# spectrometer-teensy-mk-1_0_0.net
KiCad netlist of a schematic drawn in EAGLE
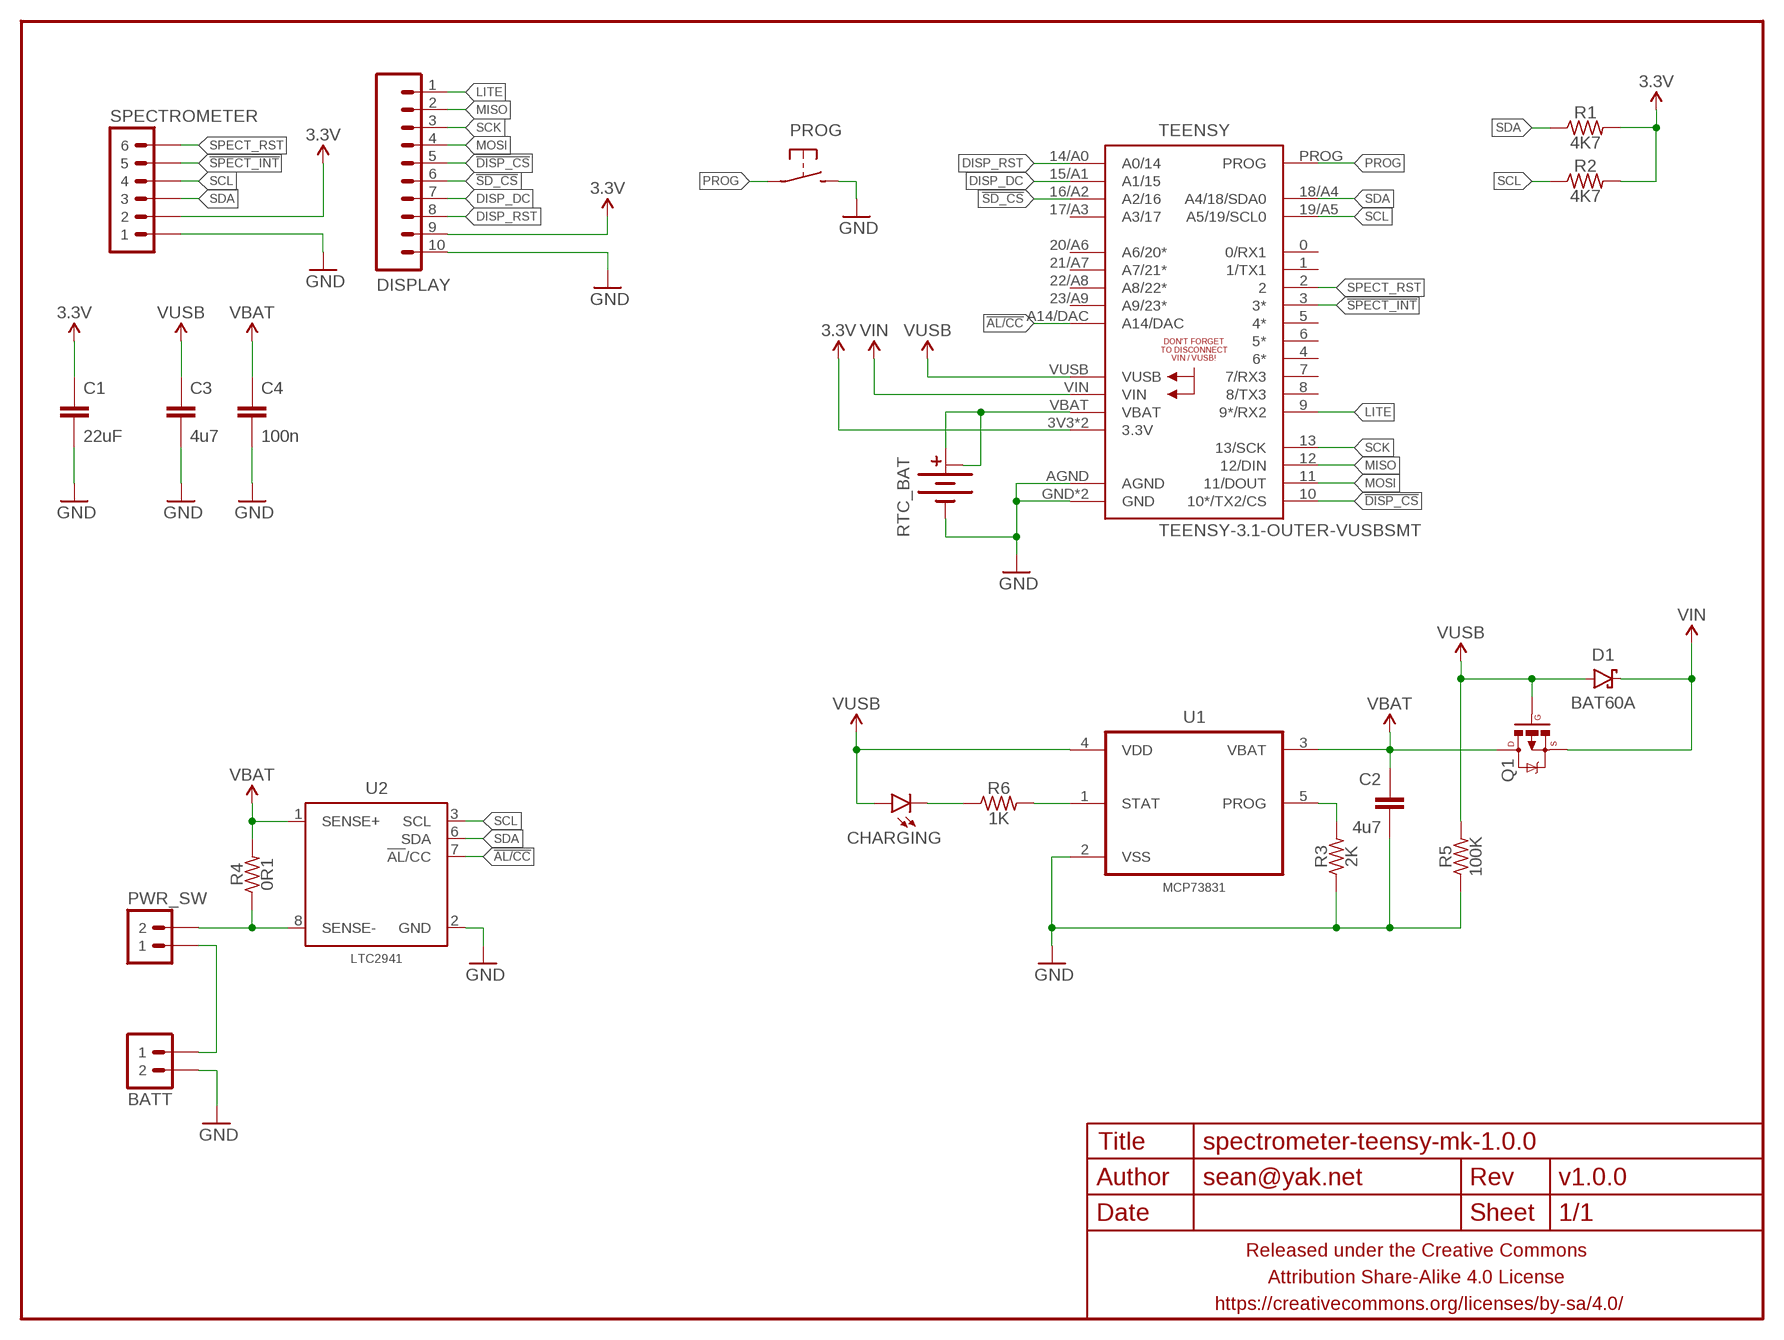
[diagram p0: schematic, sheet 1]

(export (version "E")
  (design (tool "Eeschema 10.0.6"))
  (components
    (comp (ref "BATT")
      (value "M02JST-2MM-SMT")
      (footprint "eagle-import:JST-2-SMD")
      (libsource (lib "eagle-import") (part "M02JST-2MM-SMT"))
    )
    (comp (ref "C1")
      (value "22uF")
      (footprint "eagle-import:C0805-TIGHTER")
      (libsource (lib "eagle-import") (part "CAPACITOR-CERAMICC0805-TIGHTER"))
    )
    (comp (ref "C2")
      (value "4u7")
      (footprint "eagle-import:C0603-TIGHTER")
      (libsource (lib "eagle-import") (part "CAPACITOR-CERAMICC0603-TIGHTER"))
    )
    (comp (ref "C3")
      (value "4u7")
      (footprint "eagle-import:C0603-TIGHTER")
      (libsource (lib "eagle-import") (part "CAPACITOR-CERAMICC0603-TIGHTER"))
    )
    (comp (ref "C4")
      (value "100n")
      (footprint "eagle-import:C0603-TIGHTER")
      (libsource (lib "eagle-import") (part "CAPACITOR-CERAMICC0603-TIGHTER"))
    )
    (comp (ref "CHARGING")
      (value "LED0603-TIGHT")
      (footprint "eagle-import:LED-0603-TIGHT")
      (libsource (lib "eagle-import") (part "LED0603-TIGHT"))
    )
    (comp (ref "D1")
      (value "BAT60A")
      (footprint "eagle-import:SOD123-SCHOTTKY")
      (libsource (lib "eagle-import") (part "DIODE-SCHOTTKYSOD123"))
    )
    (comp (ref "DISPLAY")
      (value "M10SMD_RA_2MM")
      (footprint "eagle-import:1X10_SMD_RA_MALE")
      (libsource (lib "eagle-import") (part "M10SMD_RA_2MM"))
    )
    (comp (ref "FRAME1")
      (value "FRAME-LETTERNO_PACKAGE")
      (footprint "eagle-import:DUMMY")
      (fields (field (name "DESIGNER") "sean@yak.net") (field (name "VERSION") "v1.0.0"))
      (libsource (lib "eagle-import") (part "FRAME-LETTERNO_PACKAGE"))
    )
    (comp (ref "PROG")
      (value "SPST-NO-TACTCK-PTS840-GK")
      (footprint "eagle-import:TACTILE-SMD-CK-PTS840-GK")
      (libsource (lib "eagle-import") (part "SPST-NO-TACTCK-PTS840-GK"))
    )
    (comp (ref "PWR_SW")
      (value "M02JST-2MM-SMT")
      (footprint "eagle-import:JST-2-SMD")
      (libsource (lib "eagle-import") (part "M02JST-2MM-SMT"))
    )
    (comp (ref "Q1")
      (value "MOSFET-PCHANNELSOT-23")
      (footprint "eagle-import:SOT23")
      (libsource (lib "eagle-import") (part "MOSFET-PCHANNELSOT-23"))
    )
    (comp (ref "R1")
      (value "4K7")
      (footprint "eagle-import:R0603-TIGHTER")
      (libsource (lib "eagle-import") (part "RESISTORR0603-TIGHTER"))
    )
    (comp (ref "R2")
      (value "4K7")
      (footprint "eagle-import:R0603-TIGHTER")
      (libsource (lib "eagle-import") (part "RESISTORR0603-TIGHTER"))
    )
    (comp (ref "R3")
      (value "2K")
      (footprint "eagle-import:R0603-TIGHTER")
      (libsource (lib "eagle-import") (part "RESISTORR0603-TIGHTER"))
    )
    (comp (ref "R4")
      (value "0R1")
      (footprint "eagle-import:R0603-TIGHTER")
      (libsource (lib "eagle-import") (part "RESISTORR0603-TIGHTER"))
    )
    (comp (ref "R5")
      (value "100K")
      (footprint "eagle-import:R0603-TIGHTER")
      (libsource (lib "eagle-import") (part "RESISTORR0603-TIGHTER"))
    )
    (comp (ref "R6")
      (value "1K")
      (footprint "eagle-import:R0603-TIGHTER")
      (libsource (lib "eagle-import") (part "RESISTORR0603-TIGHTER"))
    )
    (comp (ref "RTC_BAT")
      (value "BATTERY-COINCR1225_SMD_SMALLER")
      (footprint "eagle-import:BATTCON_12MM_SMD")
      (libsource (lib "eagle-import") (part "BATTERY-COINCR1225_SMD_SMALLER"))
    )
    (comp (ref "SPECTROMETER")
      (value "M06SMD-2MM-RA")
      (footprint "eagle-import:1X06_SMD_RA_2MM")
      (libsource (lib "eagle-import") (part "M06SMD-2MM-RA"))
    )
    (comp (ref "TEENSY")
      (value "TEENSY-3.1-OUTER-VUSBSMT")
      (footprint "eagle-import:TEENSY-3.1_SMT_BOTTOM_OUTERMOSTLY_VUSB")
      (libsource (lib "eagle-import") (part "TEENSY-3.1-OUTER-VUSBSMT"))
    )
    (comp (ref "U1")
      (value "MCP73831")
      (footprint "eagle-import:SOT95P280X145-5N")
      (fields (field (name "MPN") "MCP73831T-2ACI/OT"))
      (libsource (lib "eagle-import") (part "MCP73831T-2ACI/OT"))
    )
    (comp (ref "U2")
      (value "LTC2941")
      (footprint "eagle-import:MSOP-8")
      (libsource (lib "eagle-import") (part "LTC2941MSOP-8"))
    )
  )
  (nets
    (net (code "1") (name "/~{AL{slash}CC}") (class "Default")
      (node (ref "TEENSY") (pin "A14/DAC") (pinfunction "A14/DAC_A14/DAC") (pintype "bidirectional"))
      (node (ref "U2") (pin "7") (pinfunction "~{AL}/CC_7") (pintype "bidirectional"))
    )
    (net (code "2") (name "/~{DISP_CS}") (class "Default")
      (node (ref "DISPLAY") (pin "5") (pinfunction "5_5") (pintype "passive"))
      (node (ref "TEENSY") (pin "10") (pinfunction "10*/TX2/CS_10") (pintype "bidirectional"))
    )
    (net (code "3") (name "/~{SD_CS}") (class "Default")
      (node (ref "DISPLAY") (pin "6") (pinfunction "6_6") (pintype "passive"))
      (node (ref "TEENSY") (pin "16/A2") (pinfunction "A2/16_16/A2") (pintype "bidirectional"))
    )
    (net (code "4") (name "/~{SPECT_INT}") (class "Default")
      (node (ref "SPECTROMETER") (pin "5") (pinfunction "5_5") (pintype "passive"))
      (node (ref "TEENSY") (pin "3") (pinfunction "3*_3") (pintype "bidirectional"))
    )
    (net (code "5") (name "3.3V") (class "Default")
      (node (ref "C1") (pin "1") (pinfunction "1_1") (pintype "passive"))
      (node (ref "DISPLAY") (pin "9") (pinfunction "9_9") (pintype "passive"))
      (node (ref "R1") (pin "2") (pinfunction "2_2") (pintype "passive"))
      (node (ref "R2") (pin "2") (pinfunction "2_2") (pintype "passive"))
      (node (ref "SPECTROMETER") (pin "2") (pinfunction "2_2") (pintype "passive"))
      (node (ref "TEENSY") (pin "3V3") (pinfunction "3.3V_3V3") (pintype "bidirectional"))
      (node (ref "TEENSY") (pin "3V3@1") (pinfunction "3.3V_3V3@1") (pintype "bidirectional"))
    )
    (net (code "6") (name "DISP_DC") (class "Default")
      (node (ref "DISPLAY") (pin "7") (pinfunction "7_7") (pintype "passive"))
      (node (ref "TEENSY") (pin "15/A1") (pinfunction "A1/15_15/A1") (pintype "bidirectional"))
    )
    (net (code "7") (name "DISP_RST") (class "Default")
      (node (ref "DISPLAY") (pin "8") (pinfunction "8_8") (pintype "passive"))
      (node (ref "TEENSY") (pin "14/A0") (pinfunction "A0/14_14/A0") (pintype "bidirectional"))
    )
    (net (code "8") (name "GND") (class "Default")
      (node (ref "BATT") (pin "1") (pinfunction "2_1") (pintype "passive"))
      (node (ref "C1") (pin "2") (pinfunction "2_2") (pintype "passive"))
      (node (ref "C2") (pin "2") (pinfunction "2_2") (pintype "passive"))
      (node (ref "C3") (pin "2") (pinfunction "2_2") (pintype "passive"))
      (node (ref "C4") (pin "2") (pinfunction "2_2") (pintype "passive"))
      (node (ref "DISPLAY") (pin "10") (pinfunction "10_10") (pintype "passive"))
      (node (ref "PROG") (pin "3") (pinfunction "2_3") (pintype "passive"))
      (node (ref "PROG") (pin "4") (pinfunction "2_4") (pintype "passive"))
      (node (ref "R3") (pin "1") (pinfunction "1_1") (pintype "passive"))
      (node (ref "R5") (pin "1") (pinfunction "1_1") (pintype "passive"))
      (node (ref "RTC_BAT") (pin "-") (pinfunction "-_-") (pintype "bidirectional"))
      (node (ref "SPECTROMETER") (pin "1") (pinfunction "1_1") (pintype "passive"))
      (node (ref "TEENSY") (pin "AGND") (pinfunction "AGND_AGND") (pintype "bidirectional"))
      (node (ref "TEENSY") (pin "GND") (pinfunction "GND_GND") (pintype "bidirectional"))
      (node (ref "TEENSY") (pin "GND@1") (pinfunction "GND_GND@1") (pintype "bidirectional"))
      (node (ref "U1") (pin "2") (pinfunction "VSS_2") (pintype "power_in"))
      (node (ref "U2") (pin "2") (pinfunction "GND_2") (pintype "bidirectional"))
    )
    (net (code "9") (name "LITE") (class "Default")
      (node (ref "DISPLAY") (pin "1") (pinfunction "1_1") (pintype "passive"))
      (node (ref "TEENSY") (pin "9") (pinfunction "9*/RX2_9") (pintype "bidirectional"))
    )
    (net (code "10") (name "MISO") (class "Default")
      (node (ref "DISPLAY") (pin "2") (pinfunction "2_2") (pintype "passive"))
      (node (ref "TEENSY") (pin "12") (pinfunction "12/DIN_12") (pintype "bidirectional"))
    )
    (net (code "11") (name "MOSI") (class "Default")
      (node (ref "DISPLAY") (pin "4") (pinfunction "4_4") (pintype "passive"))
      (node (ref "TEENSY") (pin "11") (pinfunction "11/DOUT_11") (pintype "bidirectional"))
    )
    (net (code "12") (name "Net-(BATT-1)") (class "Default")
      (node (ref "BATT") (pin "2") (pinfunction "1_2") (pintype "passive"))
      (node (ref "PWR_SW") (pin "2") (pinfunction "1_2") (pintype "passive"))
    )
    (net (code "13") (name "Net-(CHARGING-PadC)") (class "Default")
      (node (ref "CHARGING") (pin "C") (pinfunction "C_C") (pintype "passive"))
      (node (ref "R6") (pin "1") (pinfunction "1_1") (pintype "passive"))
    )
    (net (code "14") (name "Net-(PWR_SW-2)") (class "Default")
      (node (ref "PWR_SW") (pin "1") (pinfunction "2_1") (pintype "passive"))
      (node (ref "R4") (pin "1") (pinfunction "1_1") (pintype "passive"))
      (node (ref "U2") (pin "8") (pinfunction "SENSE-_8") (pintype "bidirectional"))
    )
    (net (code "15") (name "Net-(RTC_BAT-+)") (class "Default")
      (node (ref "RTC_BAT") (pin "+@1") (pinfunction "+_+@1") (pintype "bidirectional"))
      (node (ref "RTC_BAT") (pin "+@2") (pinfunction "+1_+@2") (pintype "bidirectional"))
      (node (ref "TEENSY") (pin "VBAT") (pinfunction "VBAT_VBAT") (pintype "bidirectional"))
    )
    (net (code "16") (name "Net-(U1-PROG)") (class "Default")
      (node (ref "R3") (pin "2") (pinfunction "2_2") (pintype "passive"))
      (node (ref "U1") (pin "5") (pinfunction "PROG_5") (pintype "input"))
    )
    (net (code "17") (name "Net-(U1-STAT)") (class "Default")
      (node (ref "R6") (pin "2") (pinfunction "2_2") (pintype "passive"))
      (node (ref "U1") (pin "1") (pinfunction "STAT_1") (pintype "output"))
    )
    (net (code "18") (name "PROG") (class "Default")
      (node (ref "PROG") (pin "1") (pinfunction "1_1") (pintype "passive"))
      (node (ref "PROG") (pin "2") (pinfunction "1_2") (pintype "passive"))
      (node (ref "TEENSY") (pin "PROG") (pinfunction "PROG_PROG") (pintype "bidirectional"))
    )
    (net (code "19") (name "SCK") (class "Default")
      (node (ref "DISPLAY") (pin "3") (pinfunction "3_3") (pintype "passive"))
      (node (ref "TEENSY") (pin "13") (pinfunction "13/SCK_13") (pintype "bidirectional"))
    )
    (net (code "20") (name "SCL") (class "Default")
      (node (ref "R2") (pin "1") (pinfunction "1_1") (pintype "passive"))
      (node (ref "SPECTROMETER") (pin "4") (pinfunction "4_4") (pintype "passive"))
      (node (ref "TEENSY") (pin "19/A5") (pinfunction "A5/19/SCL0_19/A5") (pintype "bidirectional"))
      (node (ref "U2") (pin "3") (pinfunction "SCL_3") (pintype "bidirectional"))
    )
    (net (code "21") (name "SDA") (class "Default")
      (node (ref "R1") (pin "1") (pinfunction "1_1") (pintype "passive"))
      (node (ref "SPECTROMETER") (pin "3") (pinfunction "3_3") (pintype "passive"))
      (node (ref "TEENSY") (pin "18/A4") (pinfunction "A4/18/SDA0_18/A4") (pintype "bidirectional"))
      (node (ref "U2") (pin "6") (pinfunction "SDA_6") (pintype "bidirectional"))
    )
    (net (code "22") (name "SPECT_RST") (class "Default")
      (node (ref "SPECTROMETER") (pin "6") (pinfunction "6_6") (pintype "passive"))
      (node (ref "TEENSY") (pin "2") (pinfunction "2_2") (pintype "bidirectional"))
    )
    (net (code "23") (name "VBAT") (class "Default")
      (node (ref "C2") (pin "1") (pinfunction "1_1") (pintype "passive"))
      (node (ref "C4") (pin "1") (pinfunction "1_1") (pintype "passive"))
      (node (ref "Q1") (pin "3") (pinfunction "D_3") (pintype "passive"))
      (node (ref "R4") (pin "2") (pinfunction "2_2") (pintype "passive"))
      (node (ref "U1") (pin "3") (pinfunction "VBAT_3") (pintype "output"))
      (node (ref "U2") (pin "1") (pinfunction "SENSE+_1") (pintype "bidirectional"))
    )
    (net (code "24") (name "VIN") (class "Default")
      (node (ref "D1") (pin "C") (pinfunction "C_C") (pintype "passive"))
      (node (ref "Q1") (pin "2") (pinfunction "S_2") (pintype "passive"))
      (node (ref "TEENSY") (pin "VIN") (pinfunction "VIN_VIN") (pintype "bidirectional"))
    )
    (net (code "25") (name "VUSB") (class "Default")
      (node (ref "C3") (pin "1") (pinfunction "1_1") (pintype "passive"))
      (node (ref "CHARGING") (pin "A") (pinfunction "A_A") (pintype "passive"))
      (node (ref "D1") (pin "A") (pinfunction "A_A") (pintype "passive"))
      (node (ref "Q1") (pin "1") (pinfunction "G_1") (pintype "passive"))
      (node (ref "R5") (pin "2") (pinfunction "2_2") (pintype "passive"))
      (node (ref "TEENSY") (pin "VUSB") (pinfunction "VUSB_VUSB") (pintype "bidirectional"))
      (node (ref "U1") (pin "4") (pinfunction "VDD_4") (pintype "power_in"))
    )
    (net (code "26") (name "unconnected-(TEENSY-0{slash}RX1-Pad0)") (class "Default")
      (node (ref "TEENSY") (pin "0") (pinfunction "0/RX1_0") (pintype "bidirectional"))
    )
    (net (code "27") (name "unconnected-(TEENSY-1{slash}TX1-Pad1)") (class "Default")
      (node (ref "TEENSY") (pin "1") (pinfunction "1/TX1_1") (pintype "bidirectional"))
    )
    (net (code "28") (name "unconnected-(TEENSY-4*-Pad5)") (class "Default")
      (node (ref "TEENSY") (pin "5") (pinfunction "4*_5") (pintype "bidirectional"))
    )
    (net (code "29") (name "unconnected-(TEENSY-5*-Pad6)") (class "Default")
      (node (ref "TEENSY") (pin "6") (pinfunction "5*_6") (pintype "bidirectional"))
    )
    (net (code "30") (name "unconnected-(TEENSY-6*-Pad4)") (class "Default")
      (node (ref "TEENSY") (pin "4") (pinfunction "6*_4") (pintype "bidirectional"))
    )
    (net (code "31") (name "unconnected-(TEENSY-7{slash}RX3-Pad7)") (class "Default")
      (node (ref "TEENSY") (pin "7") (pinfunction "7/RX3_7") (pintype "bidirectional"))
    )
    (net (code "32") (name "unconnected-(TEENSY-8{slash}TX3-Pad8)") (class "Default")
      (node (ref "TEENSY") (pin "8") (pinfunction "8/TX3_8") (pintype "bidirectional"))
    )
    (net (code "33") (name "unconnected-(TEENSY-A3{slash}17-Pad17{slash}A3)") (class "Default")
      (node (ref "TEENSY") (pin "17/A3") (pinfunction "A3/17_17/A3") (pintype "bidirectional"))
    )
    (net (code "34") (name "unconnected-(TEENSY-A6{slash}20*-Pad20{slash}A6)") (class "Default")
      (node (ref "TEENSY") (pin "20/A6") (pinfunction "A6/20*_20/A6") (pintype "bidirectional"))
    )
    (net (code "35") (name "unconnected-(TEENSY-A7{slash}21*-Pad21{slash}A7)") (class "Default")
      (node (ref "TEENSY") (pin "21/A7") (pinfunction "A7/21*_21/A7") (pintype "bidirectional"))
    )
    (net (code "36") (name "unconnected-(TEENSY-A8{slash}22*-Pad22{slash}A8)") (class "Default")
      (node (ref "TEENSY") (pin "22/A8") (pinfunction "A8/22*_22/A8") (pintype "bidirectional"))
    )
    (net (code "37") (name "unconnected-(TEENSY-A9{slash}23*-Pad23{slash}A9)") (class "Default")
      (node (ref "TEENSY") (pin "23/A9") (pinfunction "A9/23*_23/A9") (pintype "bidirectional"))
    )
  )
)
